# SCH_Servo_MOSFET_Circuit_2021-11-03.net
KiCad netlist of a schematic drawn in EasyEDA
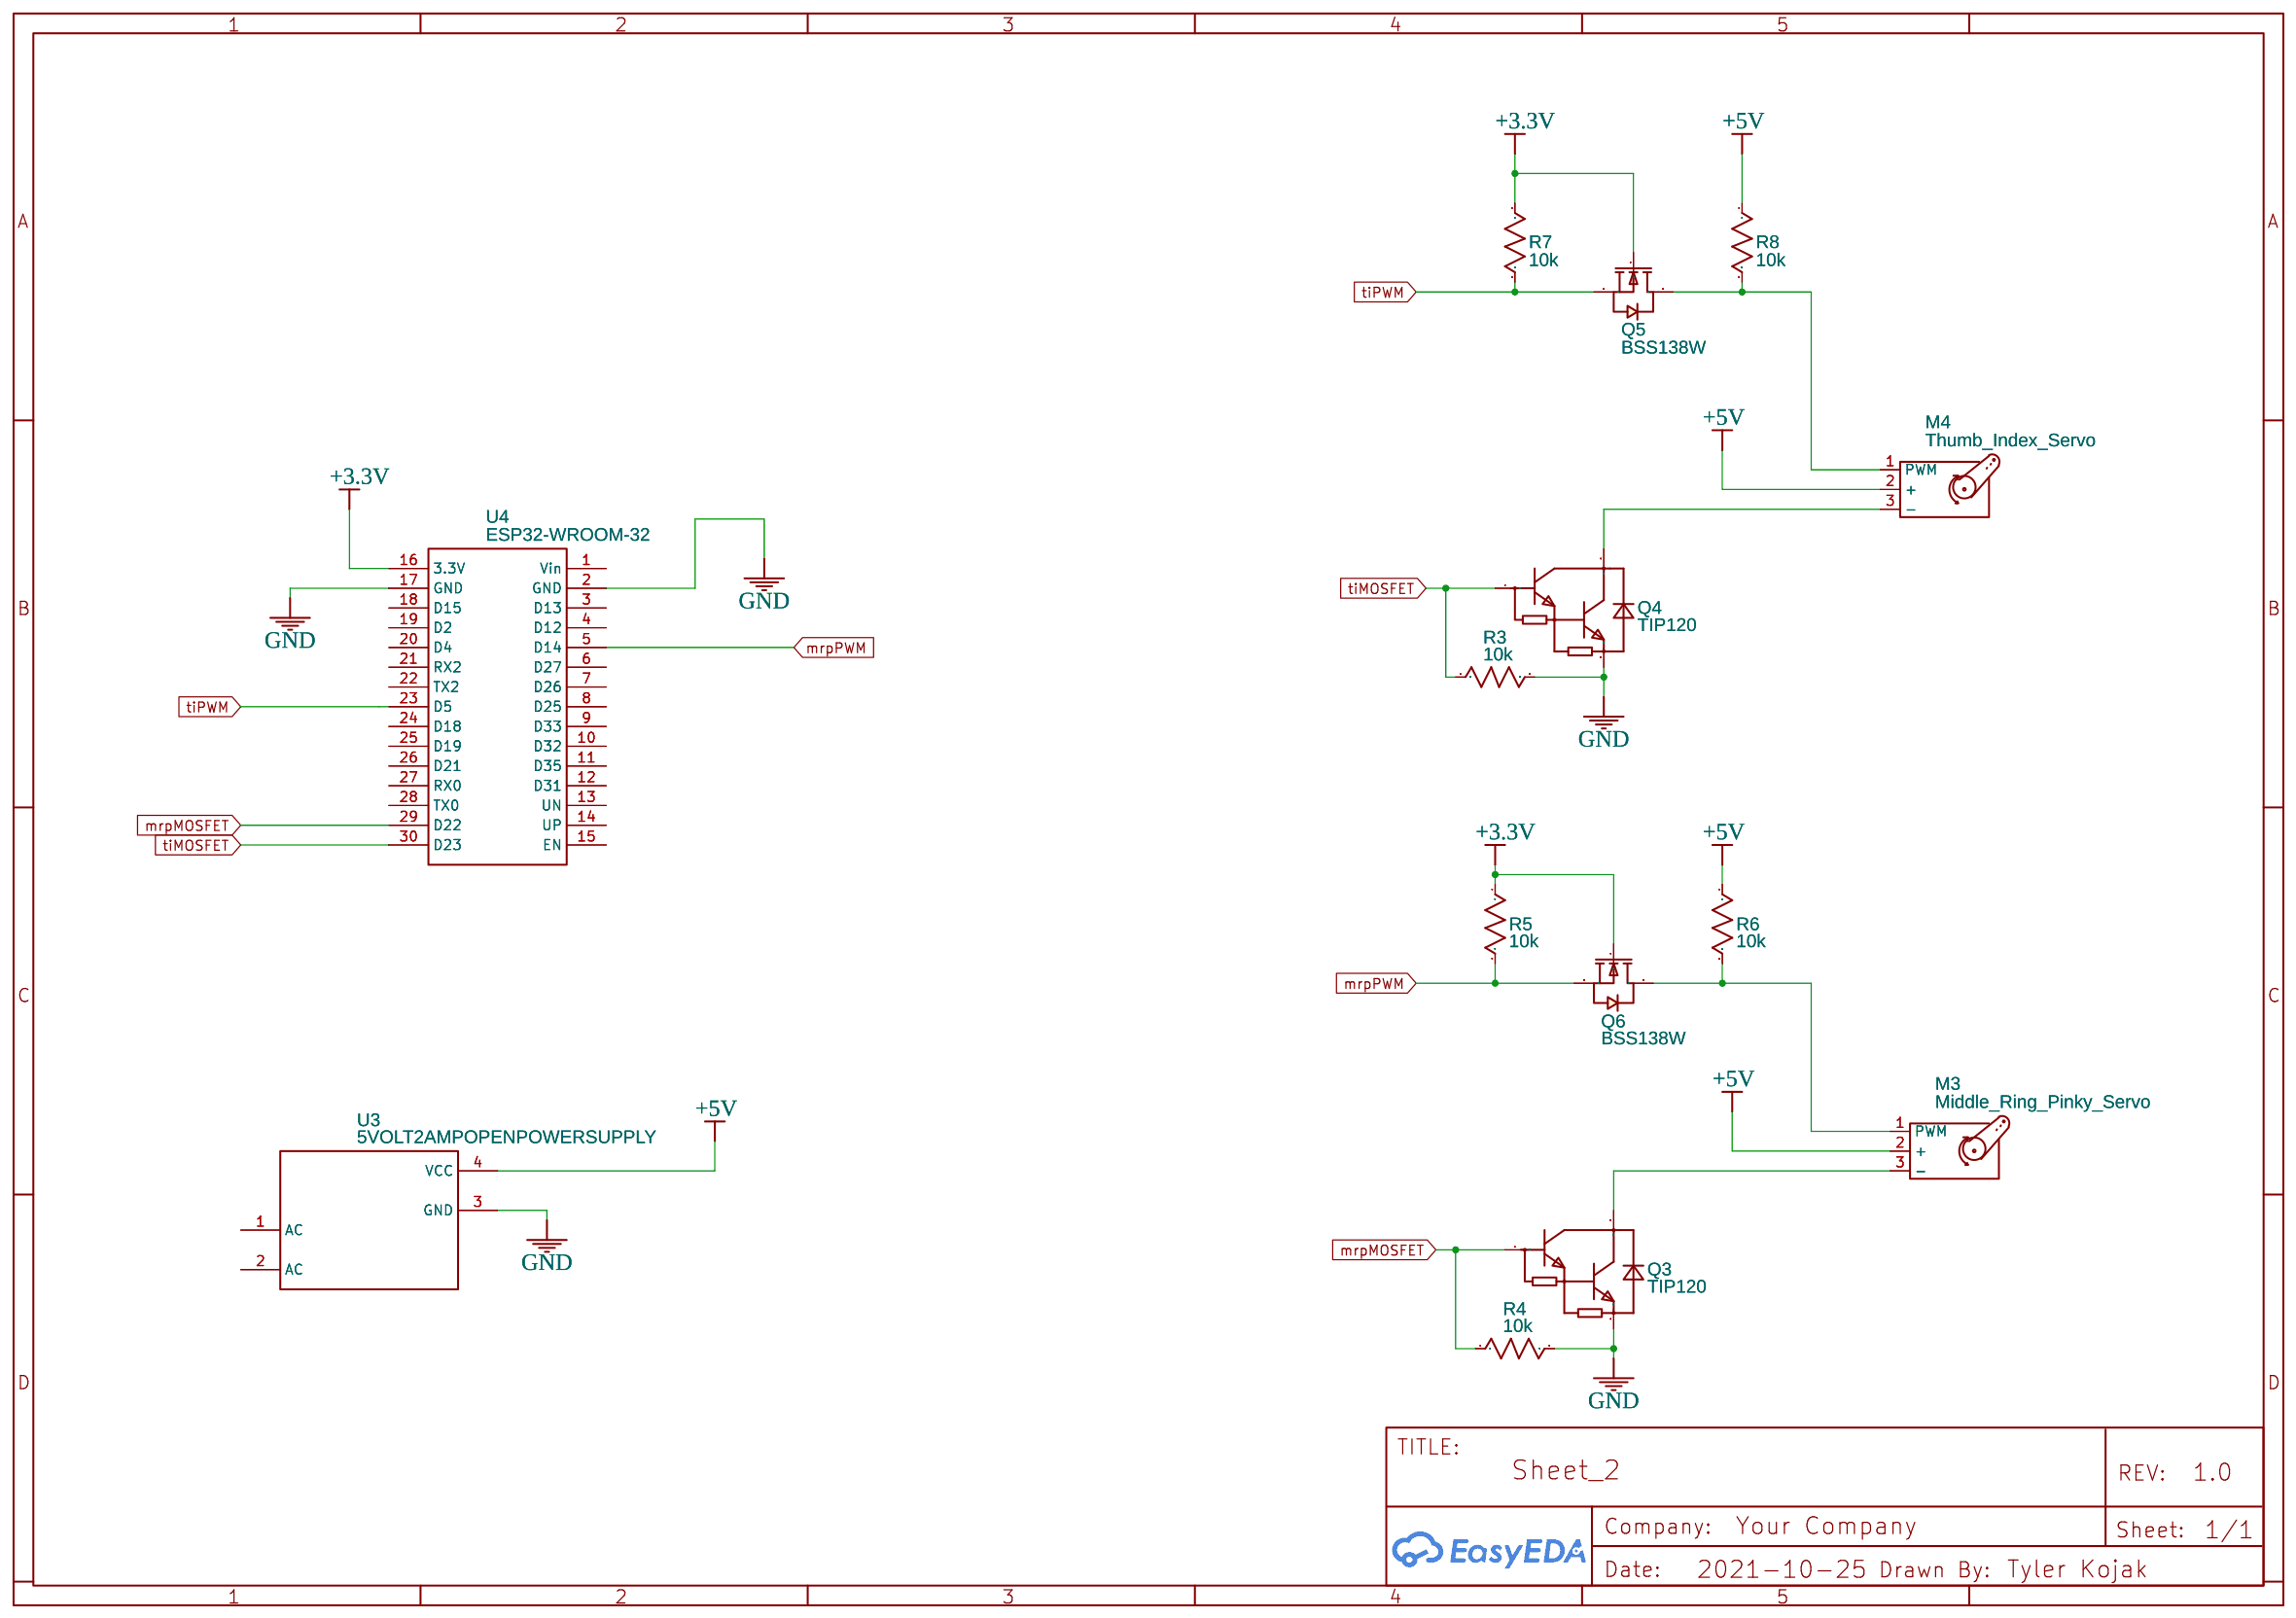
[diagram p0: Servo_Test_Schematic_BJTs]
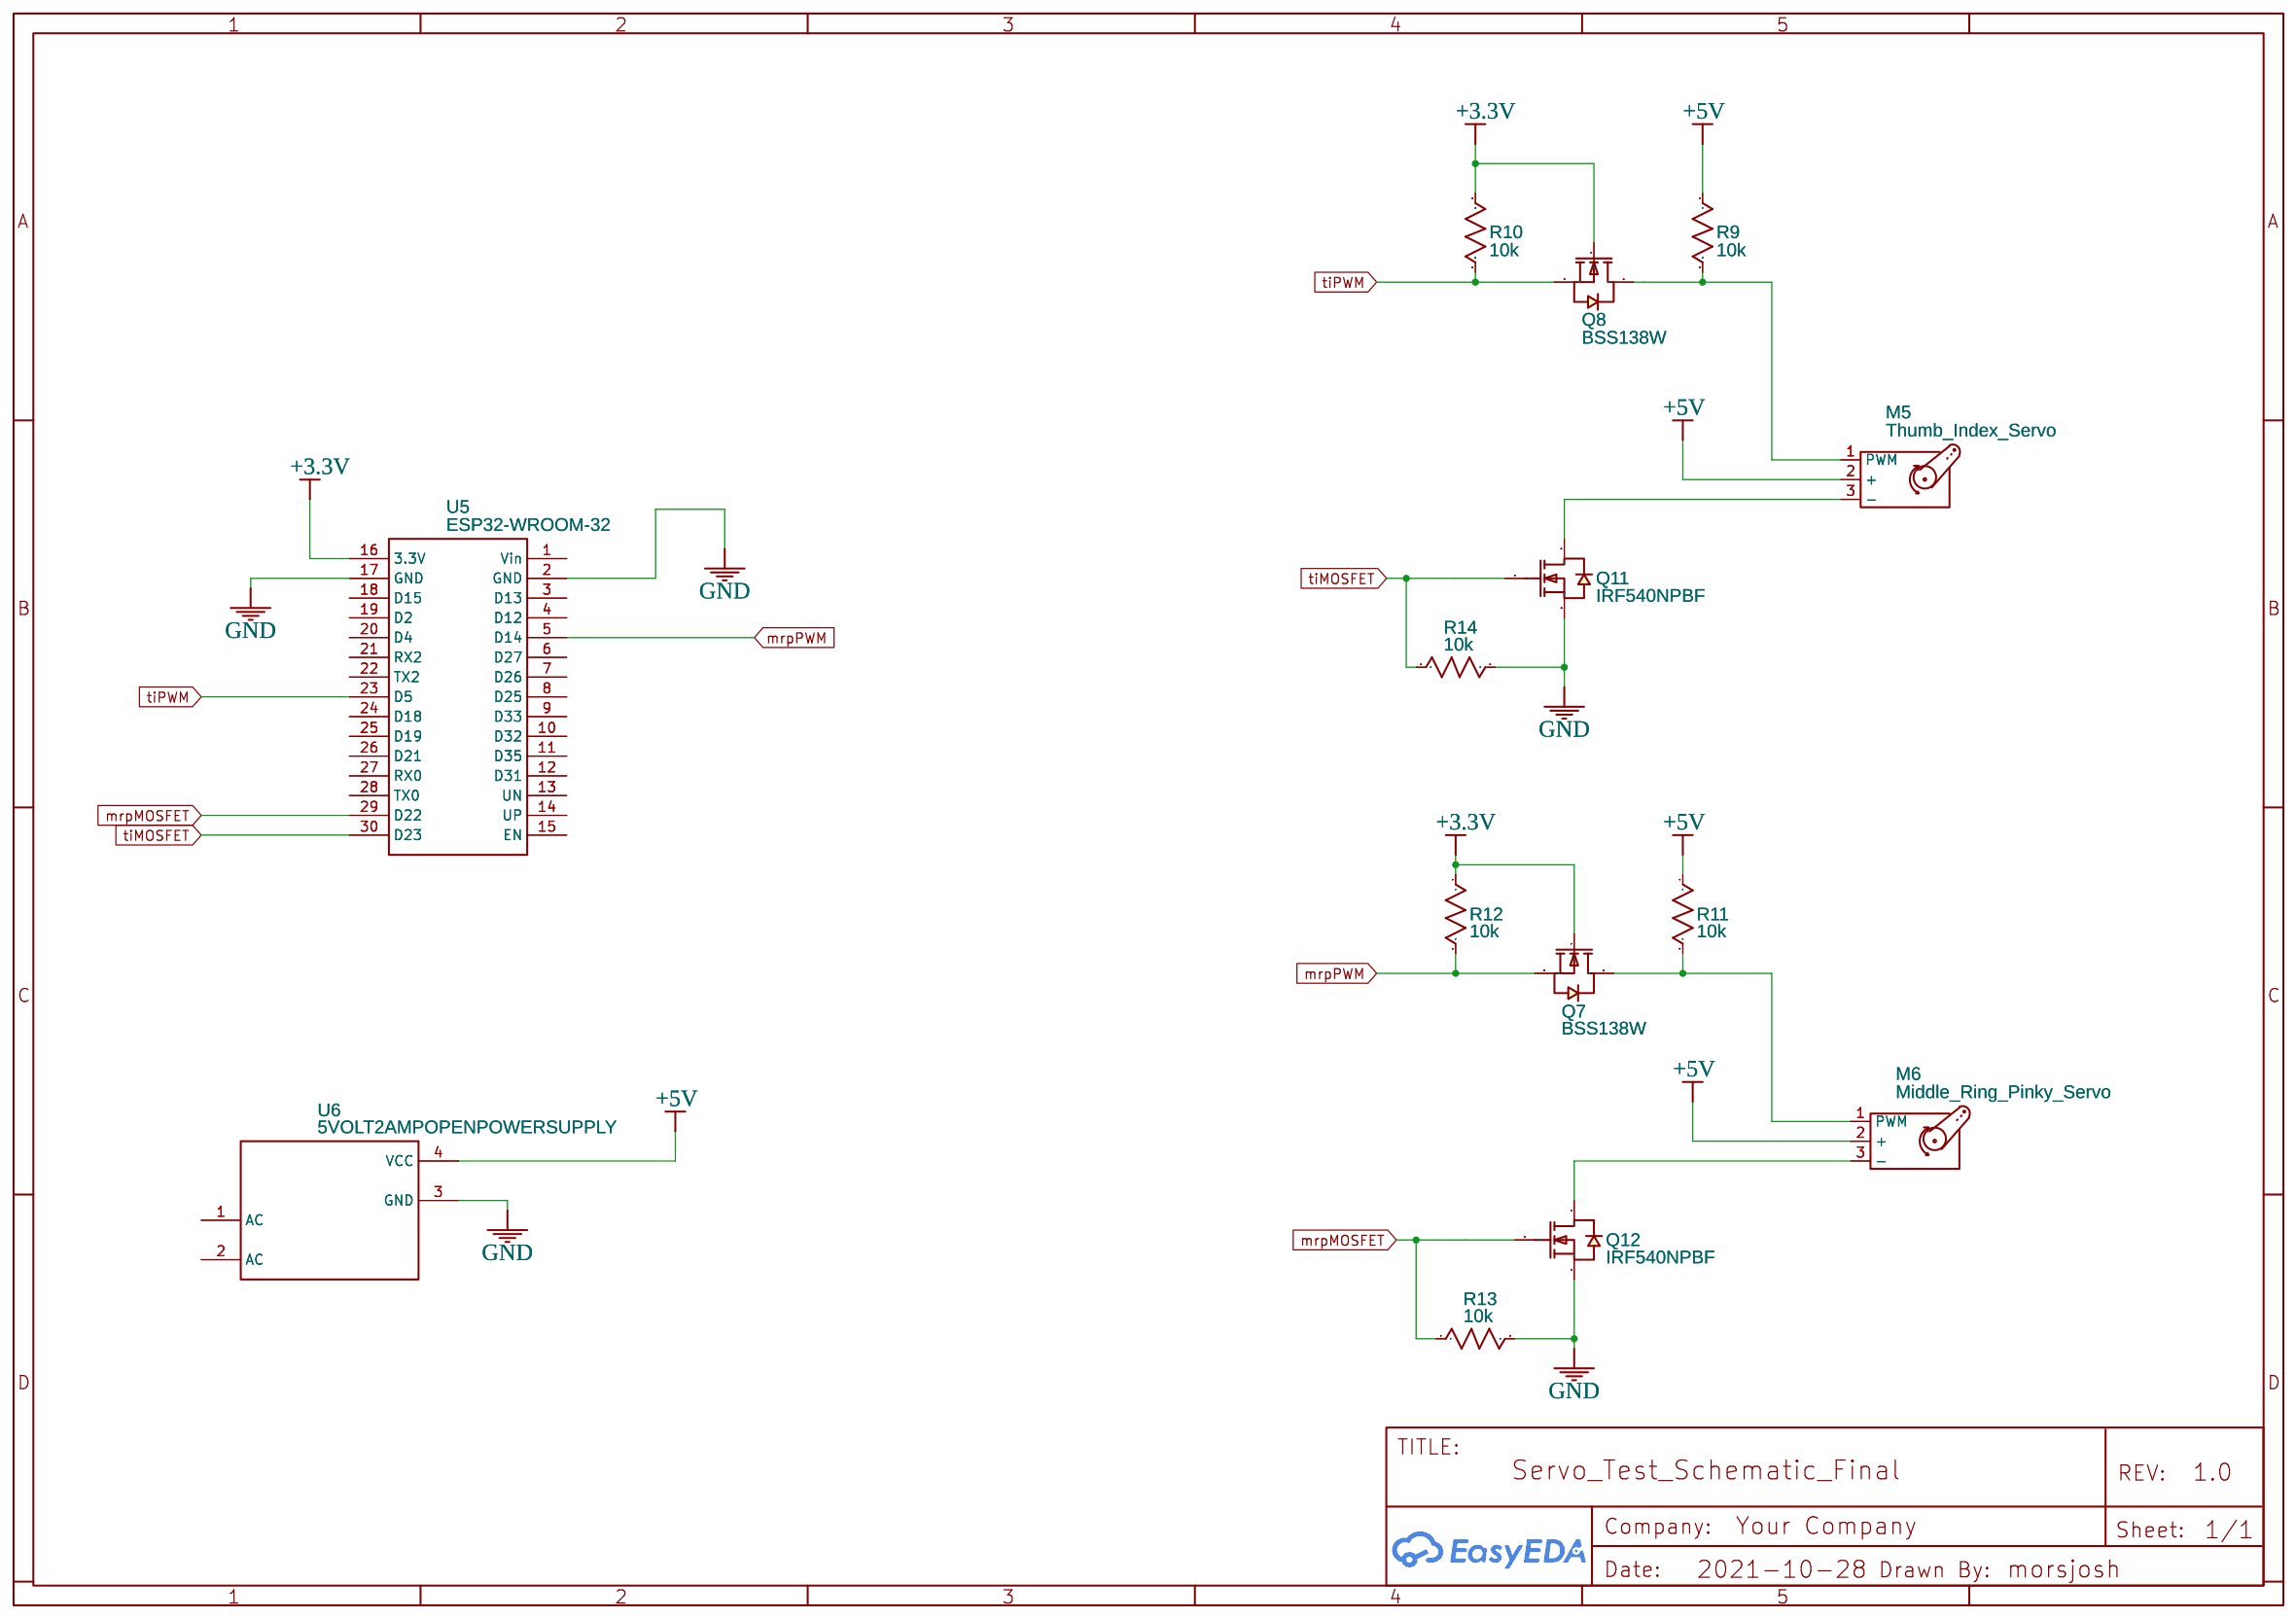
[diagram p1: Servo_Test_Schematic_MOSFETs]

(export (version "E")
  (design (tool "Eeschema 10.0.6"))
  (components
    (comp (ref "M3") (value "Middle_Ring_Pinky_Servo") (libsource (lib "") (part "Motor_Servo")))
    (comp (ref "M4") (value "Thumb_Index_Servo") (libsource (lib "") (part "Motor_Servo")))
    (comp (ref "Q3")
      (value "TIP120")
      (fields (field (name "BOM_Supplier Part") "C262990"))
      (libsource (lib "") (part "TIP120"))
    )
    (comp (ref "Q4")
      (value "TIP120")
      (fields (field (name "BOM_Supplier Part") "C262990"))
      (libsource (lib "") (part "TIP120"))
    )
    (comp (ref "Q5")
      (value "BSS138W")
      (fields (field (name "BOM_Supplier Part") "C504052"))
      (libsource (lib "") (part "BSS138W"))
    )
    (comp (ref "Q6")
      (value "BSS138W")
      (fields (field (name "BOM_Supplier Part") "C504052"))
      (libsource (lib "") (part "BSS138W"))
    )
    (comp (ref "R3") (value "10k") (libsource (lib "") (part "R_0603_US_1")))
    (comp (ref "R4") (value "10k") (libsource (lib "") (part "R_0603_US_1")))
    (comp (ref "R5") (value "10k") (libsource (lib "") (part "R_0603_US")))
    (comp (ref "R6") (value "10k") (libsource (lib "") (part "R_0603_US")))
    (comp (ref "R7") (value "10k") (libsource (lib "") (part "R_0603_US")))
    (comp (ref "R8") (value "10k") (libsource (lib "") (part "R_0603_US")))
    (comp (ref "U3")
      (value "5VOLT2AMPOPENPOWERSUPPLY")
      (libsource (lib "") (part "5VOLT2AMPOPENPOWERSUPPLY"))
    )
    (comp (ref "U4") (value "ESP32-WROOM-32") (libsource (lib "") (part "ESP32-WROOM-32")))
    (comp (ref "M5") (value "Thumb_Index_Servo") (libsource (lib "") (part "Motor_Servo")))
    (comp (ref "M6") (value "Middle_Ring_Pinky_Servo") (libsource (lib "") (part "Motor_Servo")))
    (comp (ref "Q7")
      (value "BSS138W")
      (fields (field (name "BOM_Supplier Part") "C504052"))
      (libsource (lib "") (part "BSS138W"))
    )
    (comp (ref "Q8")
      (value "BSS138W")
      (fields (field (name "BOM_Supplier Part") "C504052"))
      (libsource (lib "") (part "BSS138W"))
    )
    (comp (ref "Q11")
      (value "IRF540NPBF")
      (fields (field (name "BOM_Supplier Part") "C2566"))
      (libsource (lib "") (part "IRF540NPBF"))
    )
    (comp (ref "Q12")
      (value "IRF540NPBF")
      (fields (field (name "BOM_Supplier Part") "C2566"))
      (libsource (lib "") (part "IRF540NPBF"))
    )
    (comp (ref "R9") (value "10k") (libsource (lib "") (part "R_0603_US")))
    (comp (ref "R10") (value "10k") (libsource (lib "") (part "R_0603_US")))
    (comp (ref "R11") (value "10k") (libsource (lib "") (part "R_0603_US")))
    (comp (ref "R12") (value "10k") (libsource (lib "") (part "R_0603_US")))
    (comp (ref "R13") (value "10k") (libsource (lib "") (part "R_0603_US_1")))
    (comp (ref "R14") (value "10k") (libsource (lib "") (part "R_0603_US_1")))
    (comp (ref "U5") (value "ESP32-WROOM-32") (libsource (lib "") (part "ESP32-WROOM-32")))
    (comp (ref "U6")
      (value "5VOLT2AMPOPENPOWERSUPPLY")
      (libsource (lib "") (part "5VOLT2AMPOPENPOWERSUPPLY"))
    )
  )
  (nets
    (net (code "1") (name "+3.3V") (class "Default")
      (node (ref "Q5") (pin "1") (pinfunction "G_1") (pintype "unspecified"))
      (node (ref "Q6") (pin "1") (pinfunction "G_1") (pintype "unspecified"))
      (node (ref "Q7") (pin "1") (pinfunction "G_1") (pintype "unspecified"))
      (node (ref "Q8") (pin "1") (pinfunction "G_1") (pintype "unspecified"))
      (node (ref "R10") (pin "1") (pinfunction "1_1") (pintype "unspecified"))
      (node (ref "R12") (pin "1") (pinfunction "1_1") (pintype "unspecified"))
      (node (ref "R5") (pin "1") (pinfunction "1_1") (pintype "unspecified"))
      (node (ref "R7") (pin "1") (pinfunction "1_1") (pintype "unspecified"))
      (node (ref "U4") (pin "16") (pinfunction "3.3V_16") (pintype "unspecified"))
      (node (ref "U5") (pin "16") (pinfunction "3.3V_16") (pintype "unspecified"))
    )
    (net (code "2") (name "+5V") (class "Default")
      (node (ref "M3") (pin "2") (pinfunction "+_2") (pintype "unspecified"))
      (node (ref "M4") (pin "2") (pinfunction "+_2") (pintype "unspecified"))
      (node (ref "M5") (pin "2") (pinfunction "+_2") (pintype "unspecified"))
      (node (ref "M6") (pin "2") (pinfunction "+_2") (pintype "unspecified"))
      (node (ref "R11") (pin "1") (pinfunction "1_1") (pintype "unspecified"))
      (node (ref "R6") (pin "1") (pinfunction "1_1") (pintype "unspecified"))
      (node (ref "R8") (pin "1") (pinfunction "1_1") (pintype "unspecified"))
      (node (ref "R9") (pin "1") (pinfunction "1_1") (pintype "unspecified"))
      (node (ref "U3") (pin "4") (pinfunction "VCC_4") (pintype "unspecified"))
      (node (ref "U6") (pin "4") (pinfunction "VCC_4") (pintype "unspecified"))
    )
    (net (code "3") (name "GND") (class "Default")
      (node (ref "Q11") (pin "3") (pinfunction "S_3") (pintype "unspecified"))
      (node (ref "Q12") (pin "3") (pinfunction "S_3") (pintype "unspecified"))
      (node (ref "Q3") (pin "3") (pinfunction "E_3") (pintype "input"))
      (node (ref "Q4") (pin "3") (pinfunction "E_3") (pintype "input"))
      (node (ref "R13") (pin "2") (pinfunction "2_2") (pintype "unspecified"))
      (node (ref "R14") (pin "2") (pinfunction "2_2") (pintype "unspecified"))
      (node (ref "R3") (pin "2") (pinfunction "2_2") (pintype "unspecified"))
      (node (ref "R4") (pin "2") (pinfunction "2_2") (pintype "unspecified"))
      (node (ref "U3") (pin "3") (pinfunction "GND_3") (pintype "unspecified"))
      (node (ref "U4") (pin "17") (pinfunction "GND_17") (pintype "unspecified"))
      (node (ref "U4") (pin "2") (pinfunction "GND_2") (pintype "unspecified"))
      (node (ref "U5") (pin "17") (pinfunction "GND_17") (pintype "unspecified"))
      (node (ref "U5") (pin "2") (pinfunction "GND_2") (pintype "unspecified"))
      (node (ref "U6") (pin "3") (pinfunction "GND_3") (pintype "unspecified"))
    )
    (net (code "4") (name "Net-(M3--)") (class "Default")
      (node (ref "M3") (pin "3") (pinfunction "-_3") (pintype "unspecified"))
      (node (ref "Q3") (pin "2") (pinfunction "C_2") (pintype "input"))
    )
    (net (code "5") (name "Net-(M3-PWM)") (class "Default")
      (node (ref "M3") (pin "1") (pinfunction "PWM_1") (pintype "unspecified"))
      (node (ref "Q6") (pin "3") (pinfunction "D_3") (pintype "unspecified"))
      (node (ref "R6") (pin "2") (pinfunction "2_2") (pintype "unspecified"))
    )
    (net (code "6") (name "Net-(M4--)") (class "Default")
      (node (ref "M4") (pin "3") (pinfunction "-_3") (pintype "unspecified"))
      (node (ref "Q4") (pin "2") (pinfunction "C_2") (pintype "input"))
    )
    (net (code "7") (name "Net-(M4-PWM)") (class "Default")
      (node (ref "M4") (pin "1") (pinfunction "PWM_1") (pintype "unspecified"))
      (node (ref "Q5") (pin "3") (pinfunction "D_3") (pintype "unspecified"))
      (node (ref "R8") (pin "2") (pinfunction "2_2") (pintype "unspecified"))
    )
    (net (code "8") (name "Net-(M5--)") (class "Default")
      (node (ref "M5") (pin "3") (pinfunction "-_3") (pintype "unspecified"))
      (node (ref "Q11") (pin "2") (pinfunction "D_2") (pintype "unspecified"))
    )
    (net (code "9") (name "Net-(M5-PWM)") (class "Default")
      (node (ref "M5") (pin "1") (pinfunction "PWM_1") (pintype "unspecified"))
      (node (ref "Q8") (pin "3") (pinfunction "D_3") (pintype "unspecified"))
      (node (ref "R9") (pin "2") (pinfunction "2_2") (pintype "unspecified"))
    )
    (net (code "10") (name "Net-(M6--)") (class "Default")
      (node (ref "M6") (pin "3") (pinfunction "-_3") (pintype "unspecified"))
      (node (ref "Q12") (pin "2") (pinfunction "D_2") (pintype "unspecified"))
    )
    (net (code "11") (name "Net-(M6-PWM)") (class "Default")
      (node (ref "M6") (pin "1") (pinfunction "PWM_1") (pintype "unspecified"))
      (node (ref "Q7") (pin "3") (pinfunction "D_3") (pintype "unspecified"))
      (node (ref "R11") (pin "2") (pinfunction "2_2") (pintype "unspecified"))
    )
    (net (code "12") (name "mrpMOSFET") (class "Default")
      (node (ref "Q12") (pin "1") (pinfunction "G_1") (pintype "unspecified"))
      (node (ref "Q3") (pin "1") (pinfunction "B_1") (pintype "input"))
      (node (ref "R13") (pin "1") (pinfunction "1_1") (pintype "unspecified"))
      (node (ref "R4") (pin "1") (pinfunction "1_1") (pintype "unspecified"))
      (node (ref "U4") (pin "29") (pinfunction "D22_29") (pintype "unspecified"))
      (node (ref "U5") (pin "29") (pinfunction "D22_29") (pintype "unspecified"))
    )
    (net (code "13") (name "mrpPWM") (class "Default")
      (node (ref "Q6") (pin "2") (pinfunction "S_2") (pintype "unspecified"))
      (node (ref "Q7") (pin "2") (pinfunction "S_2") (pintype "unspecified"))
      (node (ref "R12") (pin "2") (pinfunction "2_2") (pintype "unspecified"))
      (node (ref "R5") (pin "2") (pinfunction "2_2") (pintype "unspecified"))
      (node (ref "U4") (pin "5") (pinfunction "D14_5") (pintype "unspecified"))
      (node (ref "U5") (pin "5") (pinfunction "D14_5") (pintype "unspecified"))
    )
    (net (code "14") (name "tiMOSFET") (class "Default")
      (node (ref "Q11") (pin "1") (pinfunction "G_1") (pintype "unspecified"))
      (node (ref "Q4") (pin "1") (pinfunction "B_1") (pintype "input"))
      (node (ref "R14") (pin "1") (pinfunction "1_1") (pintype "unspecified"))
      (node (ref "R3") (pin "1") (pinfunction "1_1") (pintype "unspecified"))
      (node (ref "U4") (pin "30") (pinfunction "D23_30") (pintype "unspecified"))
      (node (ref "U5") (pin "30") (pinfunction "D23_30") (pintype "unspecified"))
    )
    (net (code "15") (name "tiPWM") (class "Default")
      (node (ref "Q5") (pin "2") (pinfunction "S_2") (pintype "unspecified"))
      (node (ref "Q8") (pin "2") (pinfunction "S_2") (pintype "unspecified"))
      (node (ref "R10") (pin "2") (pinfunction "2_2") (pintype "unspecified"))
      (node (ref "R7") (pin "2") (pinfunction "2_2") (pintype "unspecified"))
      (node (ref "U4") (pin "23") (pinfunction "D5_23") (pintype "unspecified"))
      (node (ref "U5") (pin "23") (pinfunction "D5_23") (pintype "unspecified"))
    )
    (net (code "16") (name "unconnected-(U3-AC-Pad1)") (class "Default")
      (node (ref "U3") (pin "1") (pinfunction "AC_1") (pintype "unspecified"))
    )
    (net (code "17") (name "unconnected-(U3-AC-Pad2)") (class "Default")
      (node (ref "U3") (pin "2") (pinfunction "AC_2") (pintype "unspecified"))
    )
    (net (code "18") (name "unconnected-(U4-D2-Pad19)") (class "Default")
      (node (ref "U4") (pin "19") (pinfunction "D2_19") (pintype "unspecified"))
    )
    (net (code "19") (name "unconnected-(U4-D4-Pad20)") (class "Default")
      (node (ref "U4") (pin "20") (pinfunction "D4_20") (pintype "unspecified"))
    )
    (net (code "20") (name "unconnected-(U4-D12-Pad4)") (class "Default")
      (node (ref "U4") (pin "4") (pinfunction "D12_4") (pintype "unspecified"))
    )
    (net (code "21") (name "unconnected-(U4-D13-Pad3)") (class "Default")
      (node (ref "U4") (pin "3") (pinfunction "D13_3") (pintype "unspecified"))
    )
    (net (code "22") (name "unconnected-(U4-D15-Pad18)") (class "Default")
      (node (ref "U4") (pin "18") (pinfunction "D15_18") (pintype "unspecified"))
    )
    (net (code "23") (name "unconnected-(U4-D18-Pad24)") (class "Default")
      (node (ref "U4") (pin "24") (pinfunction "D18_24") (pintype "unspecified"))
    )
    (net (code "24") (name "unconnected-(U4-D19-Pad25)") (class "Default")
      (node (ref "U4") (pin "25") (pinfunction "D19_25") (pintype "unspecified"))
    )
    (net (code "25") (name "unconnected-(U4-D21-Pad26)") (class "Default")
      (node (ref "U4") (pin "26") (pinfunction "D21_26") (pintype "unspecified"))
    )
    (net (code "26") (name "unconnected-(U4-D25-Pad8)") (class "Default")
      (node (ref "U4") (pin "8") (pinfunction "D25_8") (pintype "unspecified"))
    )
    (net (code "27") (name "unconnected-(U4-D26-Pad7)") (class "Default")
      (node (ref "U4") (pin "7") (pinfunction "D26_7") (pintype "unspecified"))
    )
    (net (code "28") (name "unconnected-(U4-D27-Pad6)") (class "Default")
      (node (ref "U4") (pin "6") (pinfunction "D27_6") (pintype "unspecified"))
    )
    (net (code "29") (name "unconnected-(U4-D31-Pad12)") (class "Default")
      (node (ref "U4") (pin "12") (pinfunction "D31_12") (pintype "unspecified"))
    )
    (net (code "30") (name "unconnected-(U4-D32-Pad10)") (class "Default")
      (node (ref "U4") (pin "10") (pinfunction "D32_10") (pintype "unspecified"))
    )
    (net (code "31") (name "unconnected-(U4-D33-Pad9)") (class "Default")
      (node (ref "U4") (pin "9") (pinfunction "D33_9") (pintype "unspecified"))
    )
    (net (code "32") (name "unconnected-(U4-D35-Pad11)") (class "Default")
      (node (ref "U4") (pin "11") (pinfunction "D35_11") (pintype "unspecified"))
    )
    (net (code "33") (name "unconnected-(U4-EN-Pad15)") (class "Default")
      (node (ref "U4") (pin "15") (pinfunction "EN_15") (pintype "unspecified"))
    )
    (net (code "34") (name "unconnected-(U4-RX0-Pad27)") (class "Default")
      (node (ref "U4") (pin "27") (pinfunction "RX0_27") (pintype "unspecified"))
    )
    (net (code "35") (name "unconnected-(U4-RX2-Pad21)") (class "Default")
      (node (ref "U4") (pin "21") (pinfunction "RX2_21") (pintype "unspecified"))
    )
    (net (code "36") (name "unconnected-(U4-TX0-Pad28)") (class "Default")
      (node (ref "U4") (pin "28") (pinfunction "TX0_28") (pintype "unspecified"))
    )
    (net (code "37") (name "unconnected-(U4-TX2-Pad22)") (class "Default")
      (node (ref "U4") (pin "22") (pinfunction "TX2_22") (pintype "unspecified"))
    )
    (net (code "38") (name "unconnected-(U4-UN-Pad13)") (class "Default")
      (node (ref "U4") (pin "13") (pinfunction "UN_13") (pintype "unspecified"))
    )
    (net (code "39") (name "unconnected-(U4-UP-Pad14)") (class "Default")
      (node (ref "U4") (pin "14") (pinfunction "UP_14") (pintype "unspecified"))
    )
    (net (code "40") (name "unconnected-(U4-Vin-Pad1)") (class "Default")
      (node (ref "U4") (pin "1") (pinfunction "Vin_1") (pintype "unspecified"))
    )
    (net (code "41") (name "unconnected-(U5-D2-Pad19)") (class "Default")
      (node (ref "U5") (pin "19") (pinfunction "D2_19") (pintype "unspecified"))
    )
    (net (code "42") (name "unconnected-(U5-D4-Pad20)") (class "Default")
      (node (ref "U5") (pin "20") (pinfunction "D4_20") (pintype "unspecified"))
    )
    (net (code "43") (name "unconnected-(U5-D12-Pad4)") (class "Default")
      (node (ref "U5") (pin "4") (pinfunction "D12_4") (pintype "unspecified"))
    )
    (net (code "44") (name "unconnected-(U5-D13-Pad3)") (class "Default")
      (node (ref "U5") (pin "3") (pinfunction "D13_3") (pintype "unspecified"))
    )
    (net (code "45") (name "unconnected-(U5-D15-Pad18)") (class "Default")
      (node (ref "U5") (pin "18") (pinfunction "D15_18") (pintype "unspecified"))
    )
    (net (code "46") (name "unconnected-(U5-D18-Pad24)") (class "Default")
      (node (ref "U5") (pin "24") (pinfunction "D18_24") (pintype "unspecified"))
    )
    (net (code "47") (name "unconnected-(U5-D19-Pad25)") (class "Default")
      (node (ref "U5") (pin "25") (pinfunction "D19_25") (pintype "unspecified"))
    )
    (net (code "48") (name "unconnected-(U5-D21-Pad26)") (class "Default")
      (node (ref "U5") (pin "26") (pinfunction "D21_26") (pintype "unspecified"))
    )
    (net (code "49") (name "unconnected-(U5-D25-Pad8)") (class "Default")
      (node (ref "U5") (pin "8") (pinfunction "D25_8") (pintype "unspecified"))
    )
    (net (code "50") (name "unconnected-(U5-D26-Pad7)") (class "Default")
      (node (ref "U5") (pin "7") (pinfunction "D26_7") (pintype "unspecified"))
    )
    (net (code "51") (name "unconnected-(U5-D27-Pad6)") (class "Default")
      (node (ref "U5") (pin "6") (pinfunction "D27_6") (pintype "unspecified"))
    )
    (net (code "52") (name "unconnected-(U5-D31-Pad12)") (class "Default")
      (node (ref "U5") (pin "12") (pinfunction "D31_12") (pintype "unspecified"))
    )
    (net (code "53") (name "unconnected-(U5-D32-Pad10)") (class "Default")
      (node (ref "U5") (pin "10") (pinfunction "D32_10") (pintype "unspecified"))
    )
    (net (code "54") (name "unconnected-(U5-D33-Pad9)") (class "Default")
      (node (ref "U5") (pin "9") (pinfunction "D33_9") (pintype "unspecified"))
    )
    (net (code "55") (name "unconnected-(U5-D35-Pad11)") (class "Default")
      (node (ref "U5") (pin "11") (pinfunction "D35_11") (pintype "unspecified"))
    )
    (net (code "56") (name "unconnected-(U5-EN-Pad15)") (class "Default")
      (node (ref "U5") (pin "15") (pinfunction "EN_15") (pintype "unspecified"))
    )
    (net (code "57") (name "unconnected-(U5-RX0-Pad27)") (class "Default")
      (node (ref "U5") (pin "27") (pinfunction "RX0_27") (pintype "unspecified"))
    )
    (net (code "58") (name "unconnected-(U5-RX2-Pad21)") (class "Default")
      (node (ref "U5") (pin "21") (pinfunction "RX2_21") (pintype "unspecified"))
    )
    (net (code "59") (name "unconnected-(U5-TX0-Pad28)") (class "Default")
      (node (ref "U5") (pin "28") (pinfunction "TX0_28") (pintype "unspecified"))
    )
    (net (code "60") (name "unconnected-(U5-TX2-Pad22)") (class "Default")
      (node (ref "U5") (pin "22") (pinfunction "TX2_22") (pintype "unspecified"))
    )
    (net (code "61") (name "unconnected-(U5-UN-Pad13)") (class "Default")
      (node (ref "U5") (pin "13") (pinfunction "UN_13") (pintype "unspecified"))
    )
    (net (code "62") (name "unconnected-(U5-UP-Pad14)") (class "Default")
      (node (ref "U5") (pin "14") (pinfunction "UP_14") (pintype "unspecified"))
    )
    (net (code "63") (name "unconnected-(U5-Vin-Pad1)") (class "Default")
      (node (ref "U5") (pin "1") (pinfunction "Vin_1") (pintype "unspecified"))
    )
    (net (code "64") (name "unconnected-(U6-AC-Pad1)") (class "Default")
      (node (ref "U6") (pin "1") (pinfunction "AC_1") (pintype "unspecified"))
    )
    (net (code "65") (name "unconnected-(U6-AC-Pad2)") (class "Default")
      (node (ref "U6") (pin "2") (pinfunction "AC_2") (pintype "unspecified"))
    )
  )
)
